# subADCIn.net
KiCad netlist of a schematic drawn in Altium Designer
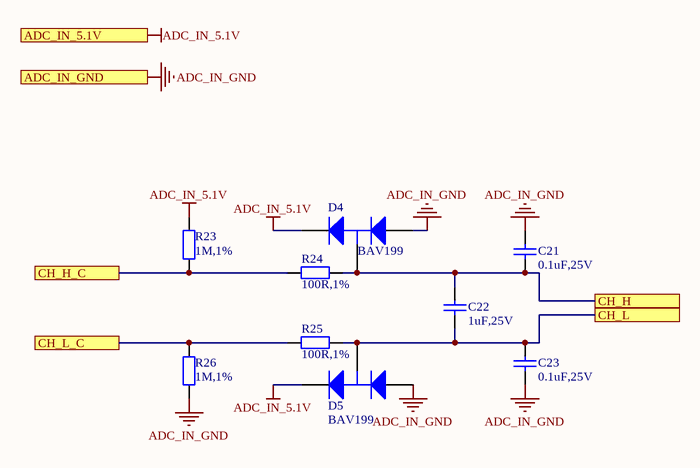
[diagram p0: subADCIn.SchDoc]

(export (version "E")
  (design (tool "Eeschema 10.0.6"))
  (components
    (comp (ref "C21")
      (value "0.1uF,25V")
      (footprint "C0603")
      (description "Capacitor")
      (libsource (lib "PCB_Symbols") (part "CAP"))
    )
    (comp (ref "C22")
      (value "1uF,25V")
      (footprint "C0603")
      (description "Capacitor")
      (libsource (lib "PCB_Symbols") (part "CAP"))
    )
    (comp (ref "C23")
      (value "0.1uF,25V")
      (footprint "C0603")
      (description "Capacitor")
      (libsource (lib "PCB_Symbols") (part "CAP"))
    )
    (comp (ref "D4")
      (value "BAV199")
      (footprint "SOT-23")
      (description "Silicon Low-Leakage Diode Array connected in series")
      (fields (field (name "PUBLISHER") "Altium Limited"))
      (libsource (lib "Infineon Discrete Diode") (part "BAV199"))
    )
    (comp (ref "D5")
      (value "BAV199")
      (footprint "SOT-23")
      (description "Silicon Low-Leakage Diode Array connected in series")
      (fields (field (name "PUBLISHER") "Altium Limited"))
      (libsource (lib "Infineon Discrete Diode") (part "BAV199"))
    )
    (comp (ref "R23")
      (value "1M,1%")
      (footprint "R0603")
      (description "电阻")
      (libsource (lib "") (part "电阻_1"))
    )
    (comp (ref "R24")
      (value "100R,1%")
      (footprint "R0603")
      (description "电阻")
      (libsource (lib "电阻电容") (part "电阻"))
    )
    (comp (ref "R25")
      (value "100R,1%")
      (footprint "R0603")
      (description "电阻")
      (libsource (lib "") (part "电阻_2"))
    )
    (comp (ref "R26")
      (value "1M,1%")
      (footprint "R0603")
      (description "电阻")
      (libsource (lib "电阻电容") (part "电阻"))
    )
  )
  (nets
    (net (code "1") (name "/CH_H") (class "Default")
      (node (ref "C21") (pin "2") (pinfunction "2_2") (pintype "passive"))
      (node (ref "C22") (pin "1") (pinfunction "1_1") (pintype "passive"))
      (node (ref "D4") (pin "3") (pinfunction "C_3") (pintype "passive"))
      (node (ref "R24") (pin "1") (pinfunction "1_1") (pintype "passive"))
    )
    (net (code "2") (name "/CH_H_C") (class "Default")
      (node (ref "R23") (pin "1") (pinfunction "1_1") (pintype "passive"))
      (node (ref "R24") (pin "2") (pinfunction "2_2") (pintype "passive"))
    )
    (net (code "3") (name "/CH_L") (class "Default")
      (node (ref "C22") (pin "2") (pinfunction "2_2") (pintype "passive"))
      (node (ref "C23") (pin "1") (pinfunction "1_1") (pintype "passive"))
      (node (ref "D5") (pin "3") (pinfunction "C_3") (pintype "passive"))
      (node (ref "R25") (pin "1") (pinfunction "1_1") (pintype "passive"))
    )
    (net (code "4") (name "/CH_L_C") (class "Default")
      (node (ref "R25") (pin "2") (pinfunction "2_2") (pintype "passive"))
      (node (ref "R26") (pin "1") (pinfunction "1_1") (pintype "passive"))
    )
    (net (code "5") (name "ADC_IN_5.1V") (class "Default")
      (node (ref "D4") (pin "2") (pinfunction "K_2") (pintype "passive"))
      (node (ref "D5") (pin "2") (pinfunction "K_2") (pintype "passive"))
      (node (ref "R23") (pin "2") (pinfunction "2_2") (pintype "passive"))
    )
    (net (code "6") (name "ADC_IN_GND") (class "Default")
      (node (ref "C21") (pin "1") (pinfunction "1_1") (pintype "passive"))
      (node (ref "C23") (pin "2") (pinfunction "2_2") (pintype "passive"))
      (node (ref "D4") (pin "1") (pinfunction "A_1") (pintype "passive"))
      (node (ref "D5") (pin "1") (pinfunction "A_1") (pintype "passive"))
      (node (ref "R26") (pin "2") (pinfunction "2_2") (pintype "passive"))
    )
  )
)
